# Solenoid_driver.net
KiCad netlist of a schematic drawn in Altium Designer
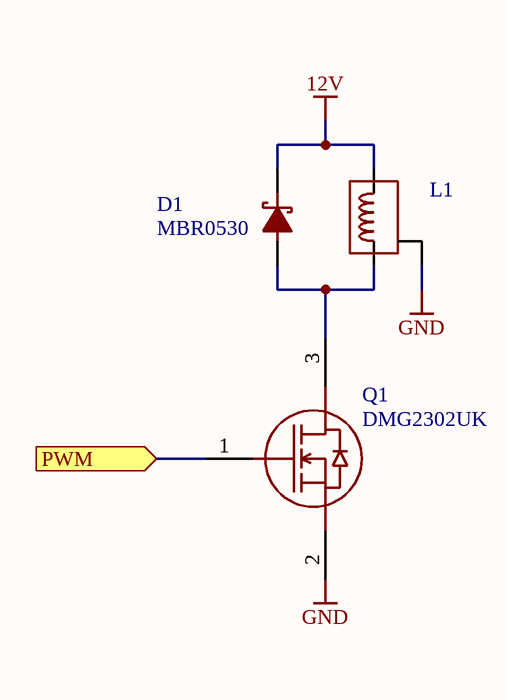
[diagram p0: Solenoid driver.SchDoc]

(export (version "E")
  (design (tool "Eeschema 10.0.6"))
  (components
    (comp (ref "D1")
      (value "MBR0530")
      (footprint "SOD-123")
      (description "Schottky Barrier Rectifier, 500mA, 30V")
      (libsource (lib "PSSL3") (part "MBR0530"))
    )
    (comp (ref "L1")
      (value "~")
      (footprint "P20/15")
      (description "Generic 806 Inductor")
      (libsource (lib "PSSL3") (part "P20/15"))
    )
    (comp (ref "Q1")
      (value "DMG2302UK")
      (footprint "SOT-23")
      (description "N-channel MOSFET")
      (libsource (lib "PSSL3") (part "DMG2302UK"))
    )
  )
  (nets
    (net (code "1") (name "/PWM") (class "Default")
      (node (ref "Q1") (pin "1") (pinfunction "G_1") (pintype "power_in"))
    )
    (net (code "2") (name "12V") (class "Default")
      (node (ref "D1") (pin "1") (pintype "passive"))
      (node (ref "L1") (pin "2") (pintype "passive"))
    )
    (net (code "3") (name "GND") (class "Default")
      (node (ref "L1") (pin "3") (pintype "passive"))
      (node (ref "Q1") (pin "2") (pinfunction "S_2") (pintype "power_in"))
    )
    (net (code "4") (name "Net-(Q1-D)") (class "Default")
      (node (ref "D1") (pin "2") (pintype "passive"))
      (node (ref "L1") (pin "1") (pintype "passive"))
      (node (ref "Q1") (pin "3") (pinfunction "D_3") (pintype "power_in"))
    )
  )
)
